# Power.net
KiCad netlist of a schematic drawn in Altium Designer
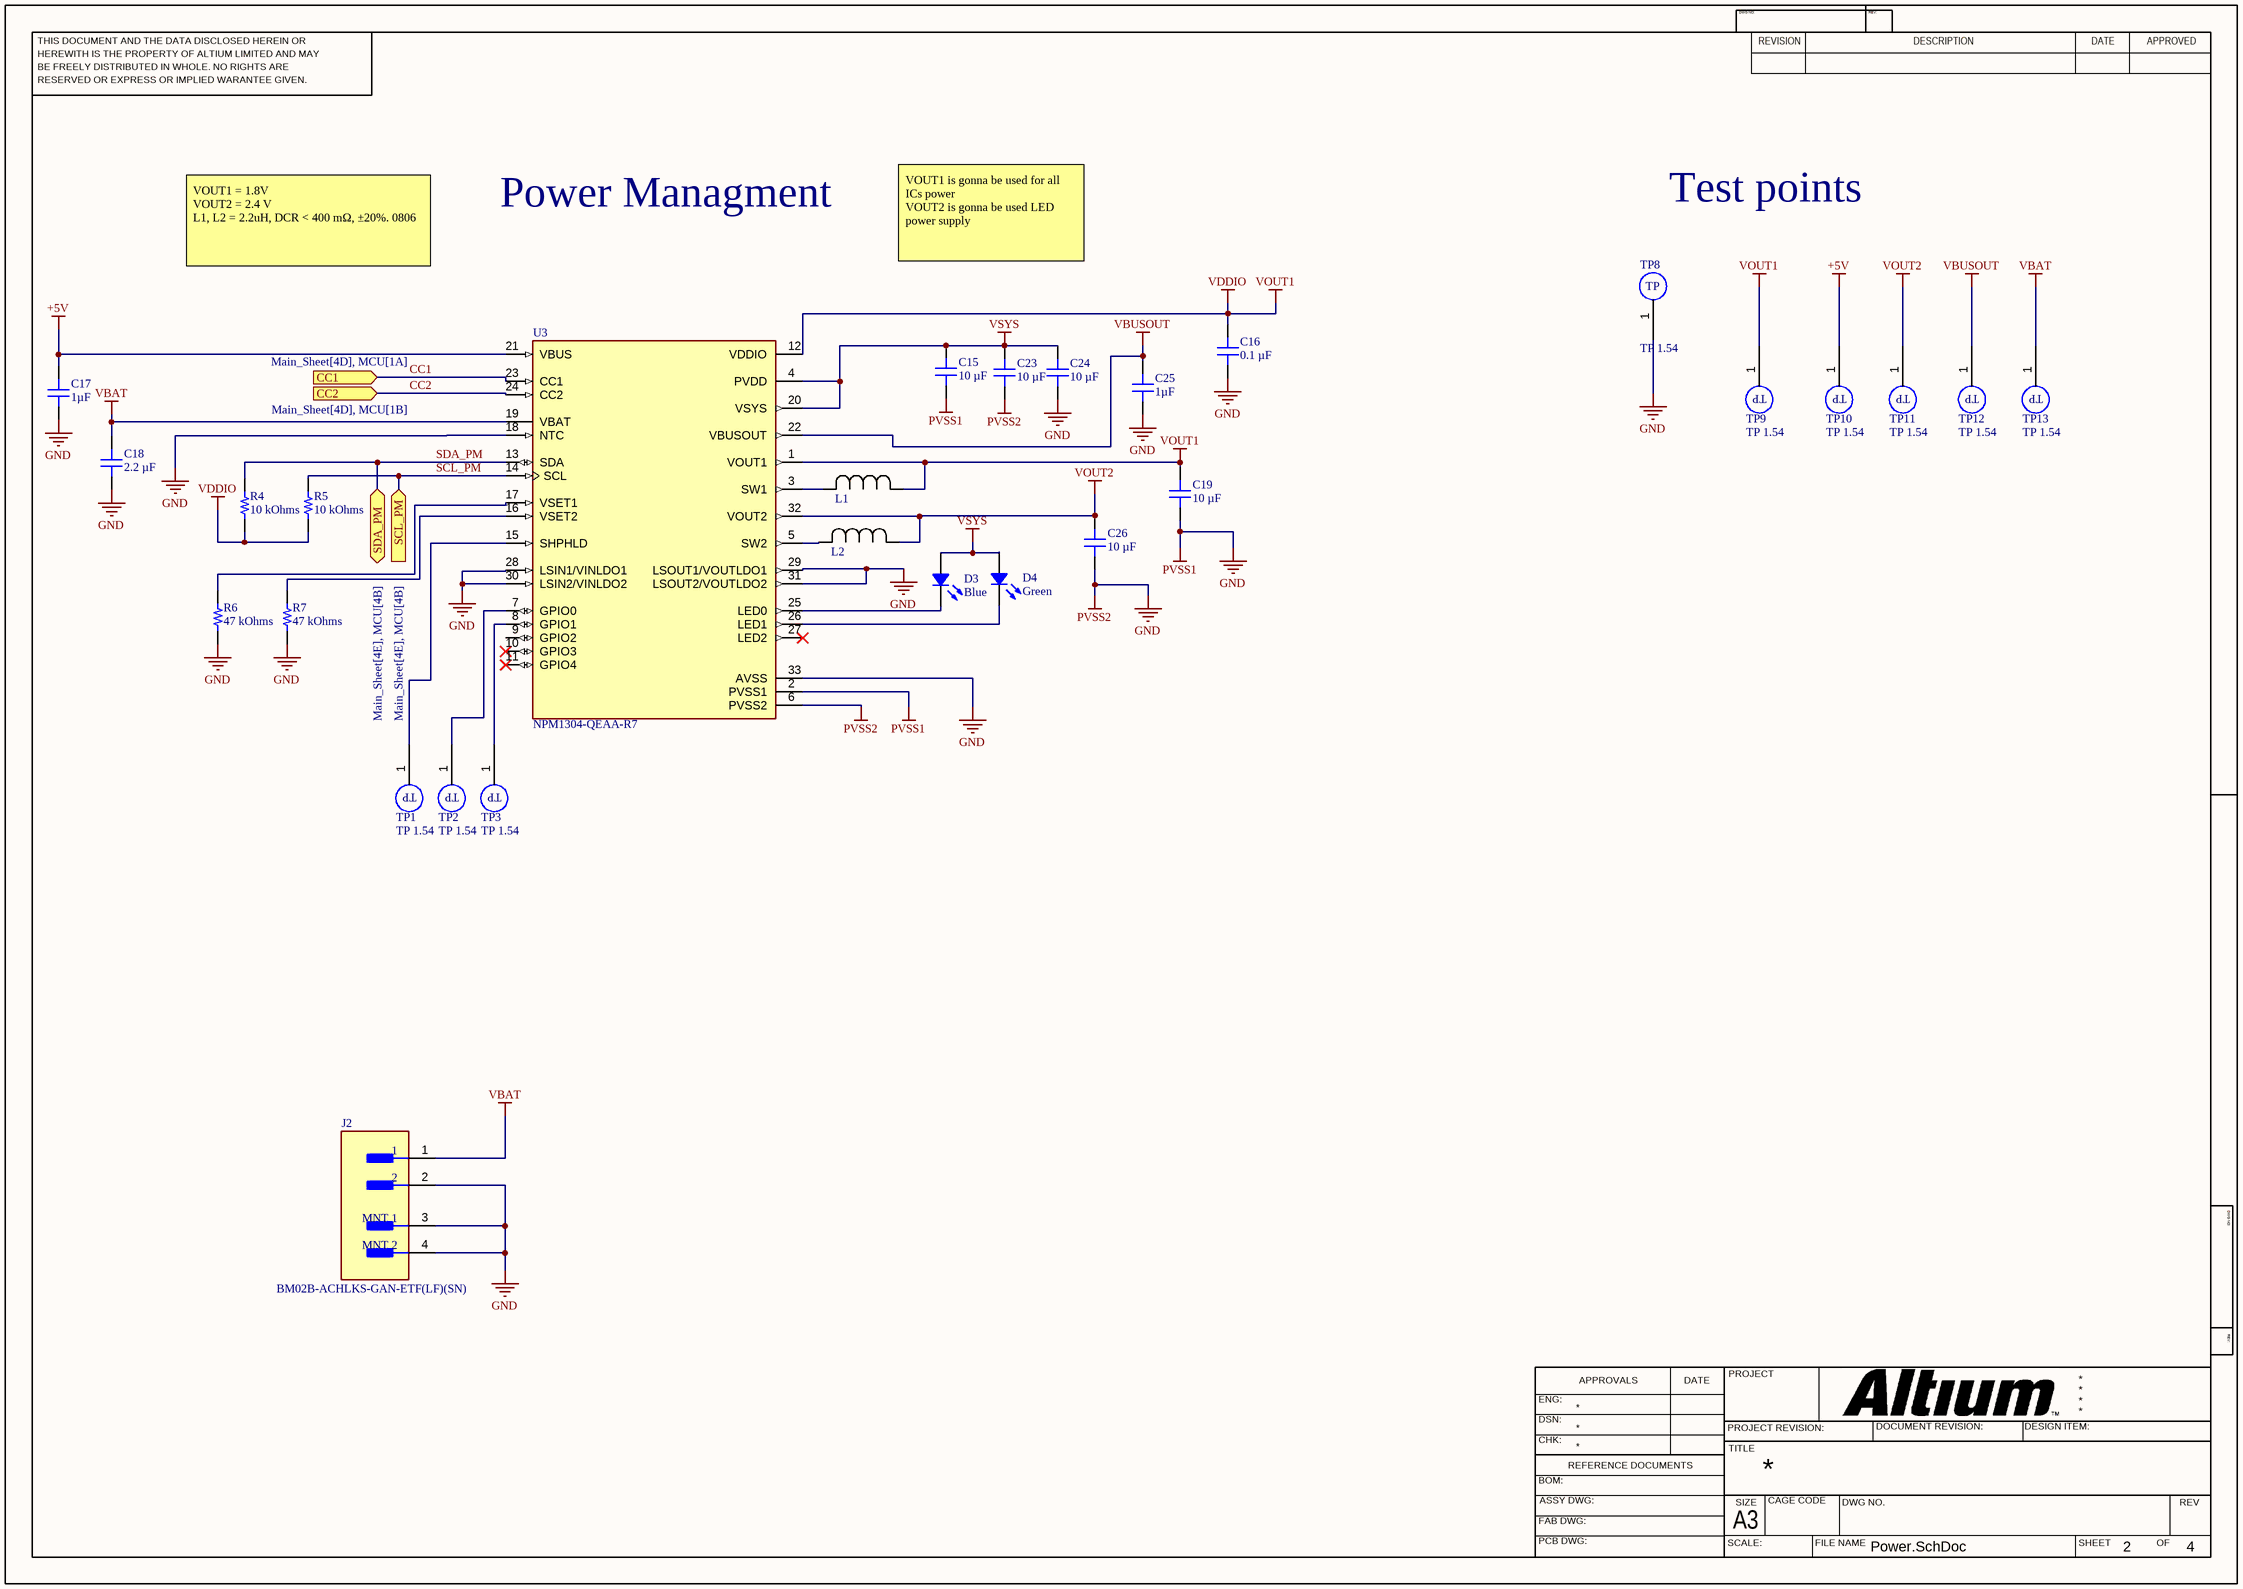
[diagram p0: Power.SchDoc]

(export (version "E")
  (design (tool "Eeschema 10.0.6"))
  (components
    (comp (ref "C15")
      (value "10 µF")
      (footprint "MURATA GRT188 0603_1608")
      (description "CAP CER 10UF 16V X5R 0603")
      (fields
        (field (name "PART NUMBER") "GRT188R61C106ME13D")
        (field (name "CAPACITANCE") "10 µF")
        (field (name "MANUFACTURER") "Murata Electronics")
      )
      (libsource (lib "Celestial Altium Library - altium_library") (part "Capacitor"))
    )
    (comp (ref "C16")
      (value "0.1 µF")
      (footprint "CAP 0402_1005")
      (description "CAP CER 100NF 10V X7R 0402")
      (fields
        (field (name "PART NUMBER") "CL05B104KP5VPNC")
        (field (name "CAPACITANCE") "0.1 µF")
        (field (name "MANUFACTURER") "Samsung Electro-Mechanics")
      )
      (libsource (lib "Celestial Altium Library - altium_library") (part "Capacitor"))
    )
    (comp (ref "C17")
      (value "1µF")
      (footprint "CAP 0603_1608")
      (description "CAP CER 1UF 25V X5R 0603")
      (fields
        (field (name "PART NUMBER") "06033D105MAT2A")
        (field (name "CAPACITANCE") "1µF")
        (field (name "MANUFACTURER") "AVX Corporation")
      )
      (libsource (lib "Celestial Altium Library - altium_library") (part "Capacitor"))
    )
    (comp (ref "C18")
      (value "2.2 µF")
      (footprint "CAP 0603_1608")
      (description "CAP CER 2.2UF 10V X5R 0603")
      (fields
        (field (name "PART NUMBER") "CGA3E3X5R1A225K080AB")
        (field (name "CAPACITANCE") "2.2 µF")
        (field (name "MANUFACTURER") "TDK Corporation")
      )
      (libsource (lib "Celestial Altium Library - altium_library") (part "Capacitor"))
    )
    (comp (ref "C19")
      (value "10 µF")
      (footprint "MURATA GRT188 0603_1608")
      (description "CAP CER 10UF 16V X5R 0603")
      (fields
        (field (name "PART NUMBER") "GRT188R61C106ME13D")
        (field (name "CAPACITANCE") "10 µF")
        (field (name "MANUFACTURER") "Murata Electronics")
      )
      (libsource (lib "Celestial Altium Library - altium_library") (part "Capacitor"))
    )
    (comp (ref "C23")
      (value "10 µF")
      (footprint "MURATA GRT188 0603_1608")
      (description "CAP CER 10UF 16V X5R 0603")
      (fields
        (field (name "PART NUMBER") "GRT188R61C106ME13D")
        (field (name "CAPACITANCE") "10 µF")
        (field (name "MANUFACTURER") "Murata Electronics")
      )
      (libsource (lib "Celestial Altium Library - altium_library") (part "Capacitor"))
    )
    (comp (ref "C24")
      (value "10 µF")
      (footprint "MURATA GRT188 0603_1608")
      (description "CAP CER 10UF 16V X5R 0603")
      (fields
        (field (name "PART NUMBER") "GRT188R61C106ME13D")
        (field (name "CAPACITANCE") "10 µF")
        (field (name "MANUFACTURER") "Murata Electronics")
      )
      (libsource (lib "Celestial Altium Library - altium_library") (part "Capacitor"))
    )
    (comp (ref "C25")
      (value "1µF")
      (footprint "CAP 0603_1608")
      (description "CAP CER 1UF 10V X5R 0603")
      (fields
        (field (name "PART NUMBER") "0603ZD105KAT4A")
        (field (name "CAPACITANCE") "1µF")
        (field (name "MANUFACTURER") "AVX Corporation")
      )
      (libsource (lib "Celestial Altium Library - altium_library") (part "Capacitor"))
    )
    (comp (ref "C26")
      (value "10 µF")
      (footprint "MURATA GRT188 0603_1608")
      (description "CAP CER 10UF 16V X5R 0603")
      (fields
        (field (name "PART NUMBER") "GRT188R61C106ME13D")
        (field (name "CAPACITANCE") "10 µF")
        (field (name "MANUFACTURER") "Murata Electronics")
      )
      (libsource (lib "Celestial Altium Library - altium_library") (part "Capacitor"))
    )
    (comp (ref "D3")
      (value "Blue")
      (footprint "LED 0402_1005 GREEN")
      (description "LED GREEN CLEAR 0402 SMD")
      (fields (field (name "PART NUMBER") "SM0402PGC") (field (name "MANUFACTURER") "Bivar Inc."))
      (libsource (lib "Celestial Altium Library - altium_library") (part "LED"))
    )
    (comp (ref "D4")
      (value "Green")
      (footprint "LED 0402_1005 GREEN")
      (description "LED GREEN CLEAR 0402 SMD")
      (fields (field (name "PART NUMBER") "SM0402PGC") (field (name "MANUFACTURER") "Bivar Inc."))
      (libsource (lib "Celestial Altium Library - altium_library") (part "LED"))
    )
    (comp (ref "J2")
      (value "BM02B-ACHLKS-GAN-ETF(LF)(SN)")
      (footprint "FP-BM02B-ACHLKS-GAN-ETF_L-MFG")
      (description "CONN HEADER SMD R/A 2POS 1.2MM")
      (libsource (lib "Altium Content Vault") (part "56ec3178a87b3978bdc1b3682cd516a"))
    )
    (comp (ref "L1")
      (value "CIGT201610EH2R2MNE")
      (footprint "IND_CIGT2016_SAM")
      (description "Description")
      (fields (field (name "COPYRIGHT") "Copyright (C) 2025 Ultra Librarian. All rights reserved."))
      (libsource (lib "Kiryl Alsheuski") (part "CIGT201610EH2R2MNE"))
    )
    (comp (ref "L2")
      (value "CIGT201610EH2R2MNE")
      (footprint "IND_CIGT2016_SAM")
      (description "Description")
      (fields (field (name "COPYRIGHT") "Copyright (C) 2025 Ultra Librarian. All rights reserved."))
      (libsource (lib "Kiryl Alsheuski") (part "CIGT201610EH2R2MNE"))
    )
    (comp (ref "R4")
      (value "10 kOhms")
      (footprint "RES 0402_1005")
      (description "RES 10K OHM 0.1% 1/10W 0402")
      (fields
        (field (name "PART NUMBER") "RP73PF1E10KBTD")
        (field (name "MANUFACTURER") "TE Connectivity Passive Product")
      )
      (libsource (lib "Celestial Altium Library - altium_library") (part "Resistor"))
    )
    (comp (ref "R5")
      (value "10 kOhms")
      (footprint "RES 0402_1005")
      (description "RES 10K OHM 0.1% 1/10W 0402")
      (fields
        (field (name "PART NUMBER") "RP73PF1E10KBTD")
        (field (name "MANUFACTURER") "TE Connectivity Passive Product")
      )
      (libsource (lib "Celestial Altium Library - altium_library") (part "Resistor"))
    )
    (comp (ref "R6")
      (value "47 kOhms")
      (footprint "RES 0402_1005")
      (description "RES 47K OHM 1% 1/16W 0402")
      (fields
        (field (name "PART NUMBER") "RMCF0402FT47K0")
        (field (name "MANUFACTURER") "Stackpole Electronics Inc")
      )
      (libsource (lib "Celestial Altium Library - altium_library") (part "Resistor"))
    )
    (comp (ref "R7")
      (value "47 kOhms")
      (footprint "RES 0402_1005")
      (description "RES 47K OHM 1% 1/16W 0402")
      (fields
        (field (name "PART NUMBER") "RMCF0402FT47K0")
        (field (name "MANUFACTURER") "Stackpole Electronics Inc")
      )
      (libsource (lib "Celestial Altium Library - altium_library") (part "Resistor"))
    )
    (comp (ref "TP1")
      (value "TP 1.54")
      (footprint "TP-Footprint-1")
      (description "Rounded rectangular pad 1.54mm")
      (libsource (lib "Kiryl Alsheuski") (part "TP-Symbol-1"))
    )
    (comp (ref "TP2")
      (value "TP 1.54")
      (footprint "TP-Footprint-1")
      (description "Rounded rectangular pad 1.54mm")
      (libsource (lib "Kiryl Alsheuski") (part "TP-Symbol-1"))
    )
    (comp (ref "TP3")
      (value "TP 1.54")
      (footprint "TP-Footprint-1")
      (description "Rounded rectangular pad 1.54mm")
      (libsource (lib "Kiryl Alsheuski") (part "TP-Symbol-1"))
    )
    (comp (ref "TP8")
      (value "TP 1.54")
      (footprint "TP-Footprint-1")
      (description "Rounded rectangular pad 1.54mm")
      (libsource (lib "Kiryl Alsheuski") (part "TP-Symbol-1"))
    )
    (comp (ref "TP9")
      (value "TP 1.54")
      (footprint "TP-Footprint-1")
      (description "Rounded rectangular pad 1.54mm")
      (libsource (lib "Kiryl Alsheuski") (part "TP-Symbol-1"))
    )
    (comp (ref "TP10")
      (value "TP 1.54")
      (footprint "TP-Footprint-1")
      (description "Rounded rectangular pad 1.54mm")
      (libsource (lib "Kiryl Alsheuski") (part "TP-Symbol-1"))
    )
    (comp (ref "TP11")
      (value "TP 1.54")
      (footprint "TP-Footprint-1")
      (description "Rounded rectangular pad 1.54mm")
      (libsource (lib "Kiryl Alsheuski") (part "TP-Symbol-1"))
    )
    (comp (ref "TP12")
      (value "TP 1.54")
      (footprint "TP-Footprint-1")
      (description "Rounded rectangular pad 1.54mm")
      (libsource (lib "Kiryl Alsheuski") (part "TP-Symbol-1"))
    )
    (comp (ref "TP13")
      (value "TP 1.54")
      (footprint "TP-Footprint-1")
      (description "Rounded rectangular pad 1.54mm")
      (libsource (lib "Kiryl Alsheuski") (part "TP-Symbol-1"))
    )
    (comp (ref "U3")
      (value "NPM1304-QEAA-R7")
      (footprint "QFN50P500X500X90-33N")
      (description "NPM1304 POWER MANAGEMENT IC")
      (fields (field (name "MF") "Nordic Semiconductor ASA"))
      (libsource (lib "Kiryl Alsheuski") (part "NPM1304-QEAA-R7"))
    )
  )
  (nets
    (net (code "1") (name "+5V") (class "Default")
      (node (ref "C17") (pin "2") (pinfunction "2_2") (pintype "passive"))
      (node (ref "TP10") (pin "1") (pinfunction "1_1") (pintype "passive"))
      (node (ref "U3") (pin "21") (pinfunction "VBUS_21") (pintype "input"))
    )
    (net (code "2") (name "/CC1") (class "Default")
      (node (ref "U3") (pin "23") (pinfunction "CC1_23") (pintype "input"))
    )
    (net (code "3") (name "/CC2") (class "Default")
      (node (ref "U3") (pin "24") (pinfunction "CC2_24") (pintype "input"))
    )
    (net (code "4") (name "/SCL_PM") (class "Default")
      (node (ref "R5") (pin "2") (pinfunction "2_2") (pintype "passive"))
      (node (ref "U3") (pin "14") (pinfunction "SCL_14") (pintype "input"))
    )
    (net (code "5") (name "/SDA_PM") (class "Default")
      (node (ref "R4") (pin "2") (pinfunction "2_2") (pintype "passive"))
      (node (ref "U3") (pin "13") (pinfunction "SDA_13") (pintype "bidirectional"))
    )
    (net (code "6") (name "GND") (class "Default")
      (node (ref "C15") (pin "1") (pinfunction "1_1") (pintype "passive"))
      (node (ref "C16") (pin "1") (pinfunction "1_1") (pintype "passive"))
      (node (ref "C17") (pin "1") (pinfunction "1_1") (pintype "passive"))
      (node (ref "C18") (pin "1") (pinfunction "1_1") (pintype "passive"))
      (node (ref "C19") (pin "1") (pinfunction "1_1") (pintype "passive"))
      (node (ref "C23") (pin "1") (pinfunction "1_1") (pintype "passive"))
      (node (ref "C24") (pin "1") (pinfunction "1_1") (pintype "passive"))
      (node (ref "C25") (pin "1") (pinfunction "1_1") (pintype "passive"))
      (node (ref "C26") (pin "1") (pinfunction "1_1") (pintype "passive"))
      (node (ref "J2") (pin "2") (pinfunction "2_2") (pintype "passive"))
      (node (ref "J2") (pin "3") (pinfunction "MNT_1_3") (pintype "passive"))
      (node (ref "J2") (pin "4") (pinfunction "MNT_2_4") (pintype "passive"))
      (node (ref "R6") (pin "1") (pinfunction "1_1") (pintype "passive"))
      (node (ref "R7") (pin "1") (pinfunction "1_1") (pintype "passive"))
      (node (ref "TP8") (pin "1") (pinfunction "1_1") (pintype "passive"))
      (node (ref "U3") (pin "18") (pinfunction "NTC_18") (pintype "input"))
      (node (ref "U3") (pin "2") (pinfunction "PVSS1_2") (pintype "power_in"))
      (node (ref "U3") (pin "28") (pinfunction "LSIN1/VINLDO1_28") (pintype "input"))
      (node (ref "U3") (pin "29") (pinfunction "LSOUT1/VOUTLDO1_29") (pintype "output"))
      (node (ref "U3") (pin "30") (pinfunction "LSIN2/VINLDO2_30") (pintype "input"))
      (node (ref "U3") (pin "31") (pinfunction "LSOUT2/VOUTLDO2_31") (pintype "output"))
      (node (ref "U3") (pin "33") (pinfunction "AVSS_33") (pintype "power_in"))
      (node (ref "U3") (pin "6") (pinfunction "PVSS2_6") (pintype "power_in"))
    )
    (net (code "7") (name "Net-(U3-GPIO0)") (class "Default")
      (node (ref "TP2") (pin "1") (pinfunction "1_1") (pintype "passive"))
      (node (ref "U3") (pin "7") (pinfunction "GPIO0_7") (pintype "bidirectional"))
    )
    (net (code "8") (name "Net-(U3-GPIO1)") (class "Default")
      (node (ref "TP3") (pin "1") (pinfunction "1_1") (pintype "passive"))
      (node (ref "U3") (pin "8") (pinfunction "GPIO1_8") (pintype "bidirectional"))
    )
    (net (code "9") (name "Net-(U3-LED0)") (class "Default")
      (node (ref "D3") (pin "2") (pinfunction "2_2") (pintype "passive"))
      (node (ref "U3") (pin "25") (pinfunction "LED0_25") (pintype "output"))
    )
    (net (code "10") (name "Net-(U3-LED1)") (class "Default")
      (node (ref "D4") (pin "2") (pinfunction "2_2") (pintype "passive"))
      (node (ref "U3") (pin "26") (pinfunction "LED1_26") (pintype "output"))
    )
    (net (code "11") (name "Net-(U3-SHPHLD)") (class "Default")
      (node (ref "TP1") (pin "1") (pinfunction "1_1") (pintype "passive"))
      (node (ref "U3") (pin "15") (pinfunction "SHPHLD_15") (pintype "input"))
    )
    (net (code "12") (name "Net-(U3-SW1)") (class "Default")
      (node (ref "L1") (pin "2") (pinfunction "2_2") (pintype "passive"))
      (node (ref "U3") (pin "3") (pinfunction "SW1_3") (pintype "output"))
    )
    (net (code "13") (name "Net-(U3-SW2)") (class "Default")
      (node (ref "L2") (pin "2") (pinfunction "2_2") (pintype "passive"))
      (node (ref "U3") (pin "5") (pinfunction "SW2_5") (pintype "output"))
    )
    (net (code "14") (name "Net-(U3-VSET1)") (class "Default")
      (node (ref "R6") (pin "2") (pinfunction "2_2") (pintype "passive"))
      (node (ref "U3") (pin "17") (pinfunction "VSET1_17") (pintype "input"))
    )
    (net (code "15") (name "Net-(U3-VSET2)") (class "Default")
      (node (ref "R7") (pin "2") (pinfunction "2_2") (pintype "passive"))
      (node (ref "U3") (pin "16") (pinfunction "VSET2_16") (pintype "input"))
    )
    (net (code "16") (name "VBAT") (class "Default")
      (node (ref "C18") (pin "2") (pinfunction "2_2") (pintype "passive"))
      (node (ref "J2") (pin "1") (pinfunction "1_1") (pintype "passive"))
      (node (ref "TP13") (pin "1") (pinfunction "1_1") (pintype "passive"))
      (node (ref "U3") (pin "19") (pinfunction "VBAT_19") (pintype "power_in"))
    )
    (net (code "17") (name "VBUSOUT") (class "Default")
      (node (ref "C25") (pin "2") (pinfunction "2_2") (pintype "passive"))
      (node (ref "TP12") (pin "1") (pinfunction "1_1") (pintype "passive"))
      (node (ref "U3") (pin "22") (pinfunction "VBUSOUT_22") (pintype "output"))
    )
    (net (code "18") (name "VDDIO") (class "Default")
      (node (ref "C16") (pin "2") (pinfunction "2_2") (pintype "passive"))
      (node (ref "C19") (pin "2") (pinfunction "2_2") (pintype "passive"))
      (node (ref "L1") (pin "1") (pinfunction "1_1") (pintype "passive"))
      (node (ref "R4") (pin "1") (pinfunction "1_1") (pintype "passive"))
      (node (ref "R5") (pin "1") (pinfunction "1_1") (pintype "passive"))
      (node (ref "TP9") (pin "1") (pinfunction "1_1") (pintype "passive"))
      (node (ref "U3") (pin "1") (pinfunction "VOUT1_1") (pintype "output"))
      (node (ref "U3") (pin "12") (pinfunction "VDDIO_12") (pintype "power_in"))
    )
    (net (code "19") (name "VOUT2") (class "Default")
      (node (ref "C26") (pin "2") (pinfunction "2_2") (pintype "passive"))
      (node (ref "L2") (pin "1") (pinfunction "1_1") (pintype "passive"))
      (node (ref "TP11") (pin "1") (pinfunction "1_1") (pintype "passive"))
      (node (ref "U3") (pin "32") (pinfunction "VOUT2_32") (pintype "output"))
    )
    (net (code "20") (name "VSYS") (class "Default")
      (node (ref "C15") (pin "2") (pinfunction "2_2") (pintype "passive"))
      (node (ref "C23") (pin "2") (pinfunction "2_2") (pintype "passive"))
      (node (ref "C24") (pin "2") (pinfunction "2_2") (pintype "passive"))
      (node (ref "D3") (pin "1") (pinfunction "1_1") (pintype "passive"))
      (node (ref "D4") (pin "1") (pinfunction "1_1") (pintype "passive"))
      (node (ref "U3") (pin "20") (pinfunction "VSYS_20") (pintype "output"))
      (node (ref "U3") (pin "4") (pinfunction "PVDD_4") (pintype "power_in"))
    )
    (net (code "21") (name "unconnected-(U3-GPIO2-Pad9)") (class "Default")
      (node (ref "U3") (pin "9") (pinfunction "GPIO2_9") (pintype "bidirectional"))
    )
    (net (code "22") (name "unconnected-(U3-GPIO3-Pad10)") (class "Default")
      (node (ref "U3") (pin "10") (pinfunction "GPIO3_10") (pintype "bidirectional+no_connect"))
    )
    (net (code "23") (name "unconnected-(U3-GPIO4-Pad11)") (class "Default")
      (node (ref "U3") (pin "11") (pinfunction "GPIO4_11") (pintype "bidirectional+no_connect"))
    )
    (net (code "24") (name "unconnected-(U3-LED2-Pad27)") (class "Default")
      (node (ref "U3") (pin "27") (pinfunction "LED2_27") (pintype "output+no_connect"))
    )
  )
)
